# PIC32MZ_BOARD.net
KiCad netlist of a schematic drawn in Altium Designer
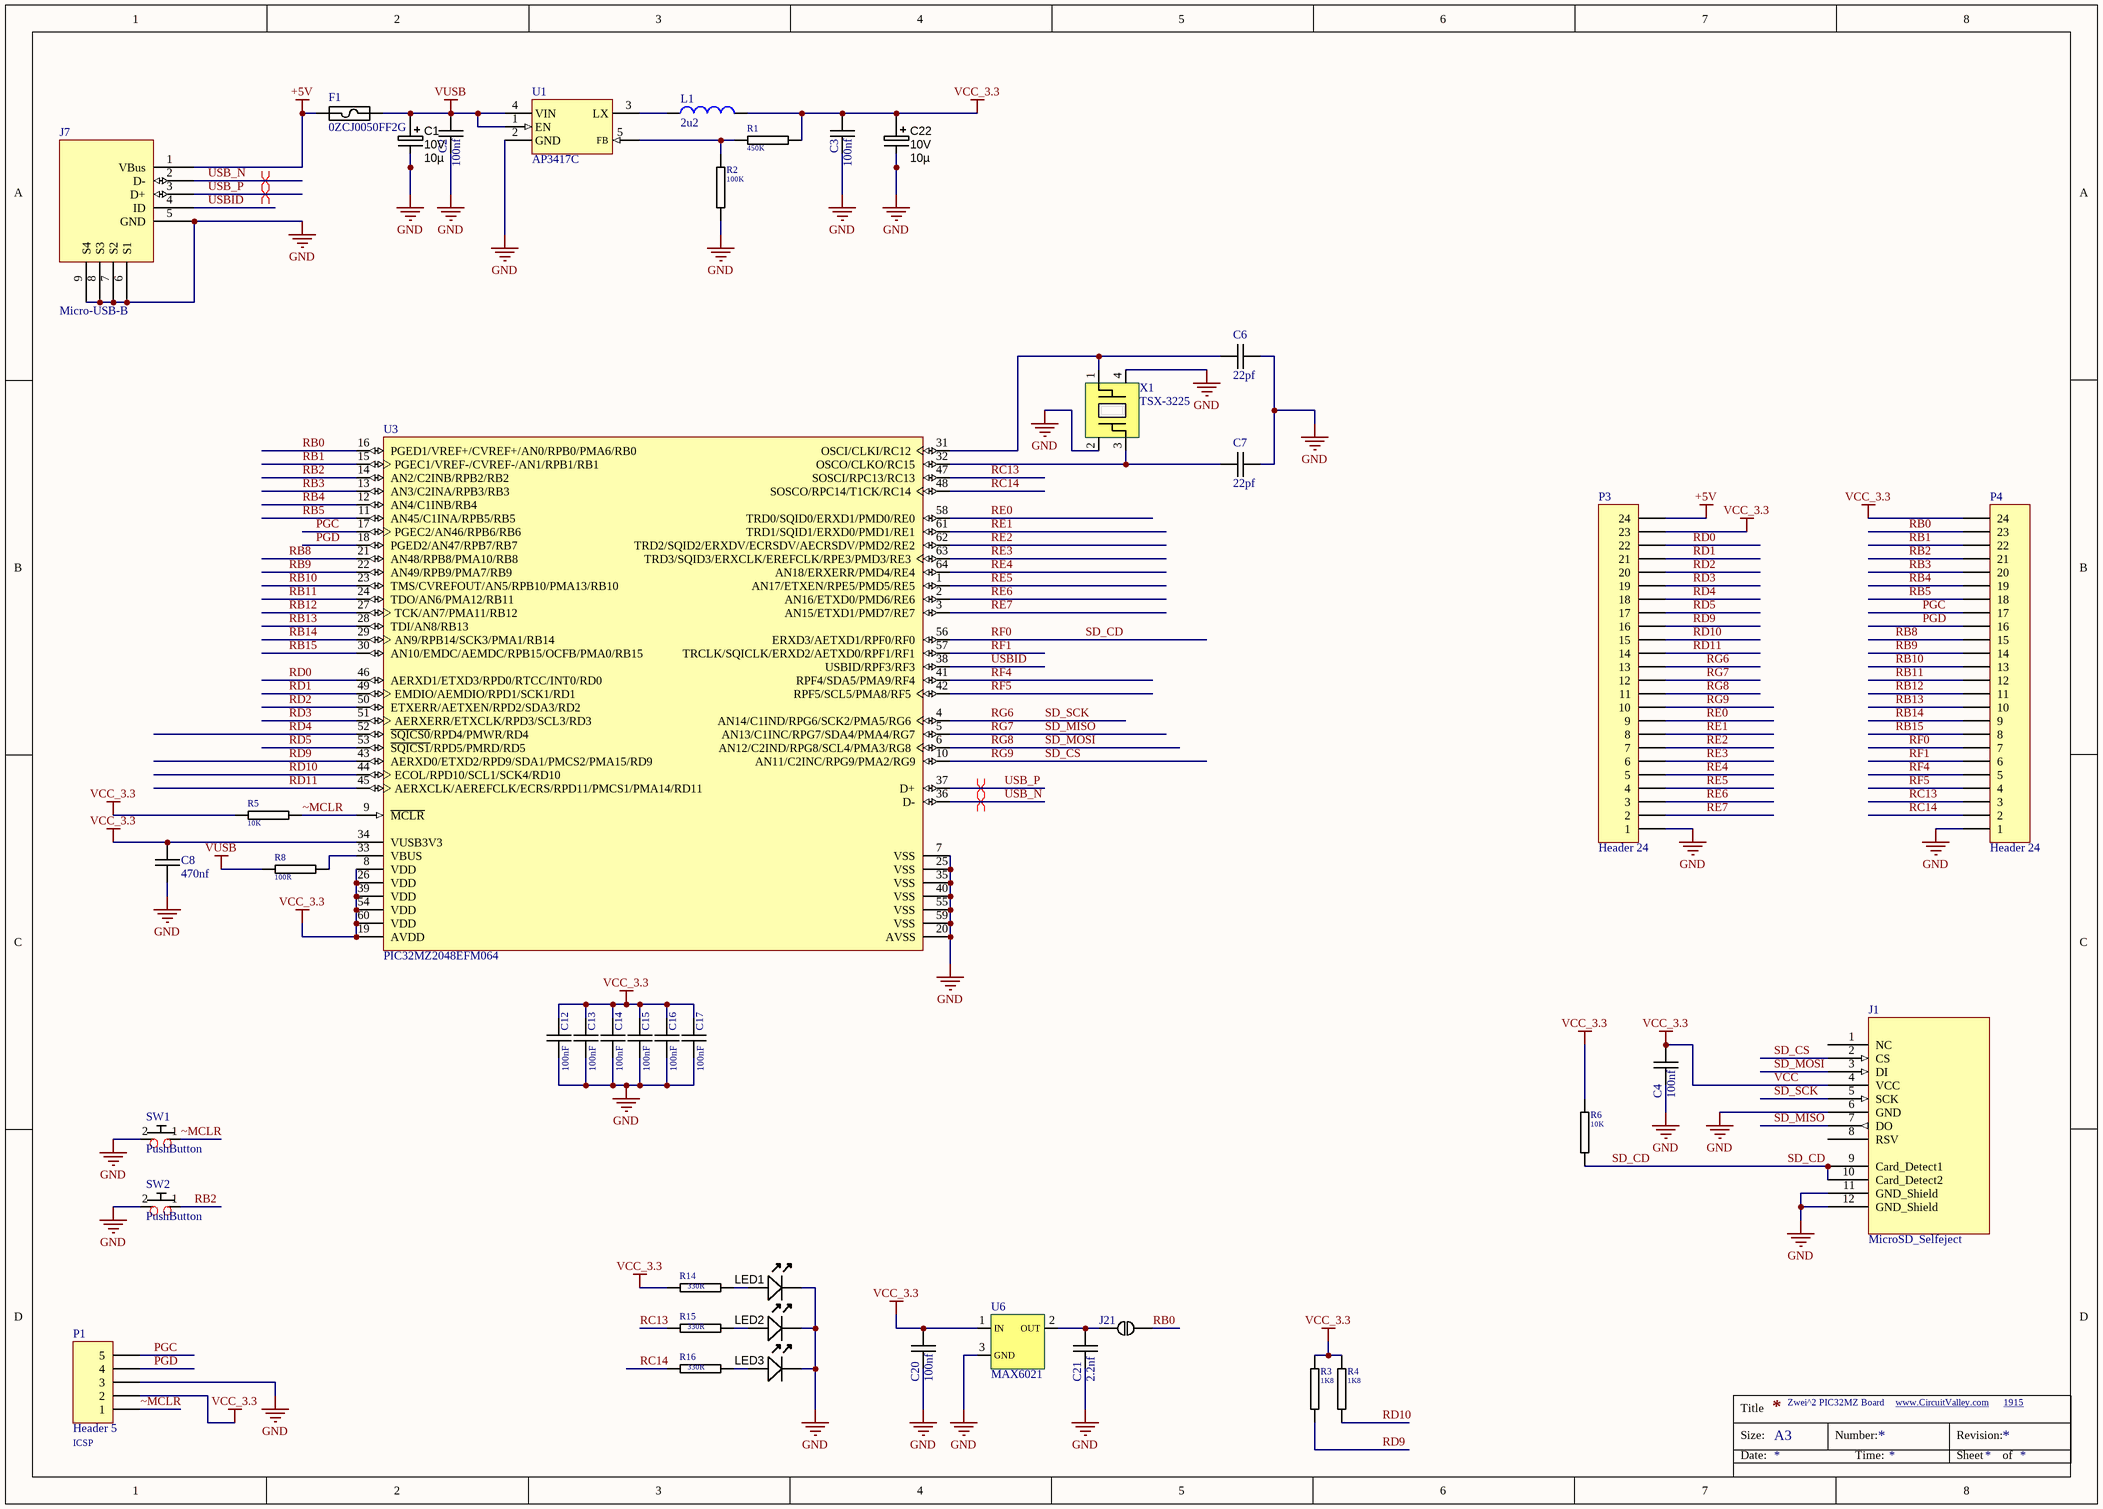
[diagram p0: PIC32MZ_BOARD.SchDoc]

(export (version "E")
  (design (tool "Eeschema 10.0.6"))
  (components
    (comp (ref "C1")
      (value "10µ")
      (footprint "CAPMP3528X210N")
      (description "Capacitor SMD Tantalum 47uF 20% 6.3V 1210")
      (fields (field (name "TOLERANCE") "±20%") (field (name "RATINGS") "10V"))
      (libsource (lib "PBL - Capacitors") (part "CAPT_47u_1210_6V3"))
    )
    (comp (ref "C2")
      (value "100nf")
      (footprint "0603C-GENERIC")
      (description "CAPACITOR 0603 CERAMIC")
      (fields
        (field (name "MANUFACTURER") "Murata Electronics North America")
        (field (name "MANUFACTURER PART NUMBER") "GRM188R60J106ME47D")
      )
      (libsource (lib "Generic") (part "0603C-10UF-6V3-X5R-MUR"))
    )
    (comp (ref "C3")
      (value "100nf")
      (footprint "0603C-GENERIC")
      (description "CAPACITOR 0603 CERAMIC")
      (fields
        (field (name "MANUFACTURER") "Murata Electronics North America")
        (field (name "MANUFACTURER PART NUMBER") "GRM188R60J106ME47D")
      )
      (libsource (lib "Generic") (part "0603C-10UF-6V3-X5R-MUR"))
    )
    (comp (ref "C4")
      (value "100nf")
      (footprint "0603C-GENERIC")
      (description "CAPACITOR 0603 CERAMIC")
      (fields
        (field (name "MANUFACTURER") "Murata Electronics North America")
        (field (name "MANUFACTURER PART NUMBER") "GRM188R60J106ME47D")
      )
      (libsource (lib "Generic") (part "0603C-10UF-6V3-X5R-MUR"))
    )
    (comp (ref "C6")
      (value "22pf")
      (footprint "0603C-GENERIC")
      (description "CAPACITOR 0603 CERAMIC")
      (fields
        (field (name "MANUFACTURER") "Murata Electronics North America")
        (field (name "MANUFACTURER PART NUMBER") "GRM188R60J106ME47D")
      )
      (libsource (lib "Generic") (part "0603C-10UF-6V3-X5R-MUR"))
    )
    (comp (ref "C7")
      (value "22pf")
      (footprint "0603C-GENERIC")
      (description "CAPACITOR 0603 CERAMIC")
      (fields
        (field (name "MANUFACTURER") "Murata Electronics North America")
        (field (name "MANUFACTURER PART NUMBER") "GRM188R60J106ME47D")
      )
      (libsource (lib "Generic") (part "0603C-10UF-6V3-X5R-MUR"))
    )
    (comp (ref "C8")
      (value "470nf")
      (footprint "0603C-GENERIC")
      (description "CAPACITOR 0603 CERAMIC")
      (fields
        (field (name "MANUFACTURER") "Murata Electronics North America")
        (field (name "MANUFACTURER PART NUMBER") "GRM188R60J106ME47D")
      )
      (libsource (lib "Generic") (part "0603C-10UF-6V3-X5R-MUR"))
    )
    (comp (ref "C12")
      (value "100nF")
      (footprint "0603C-GENERIC")
      (description "CAPACITOR 0603 CERAMIC")
      (fields
        (field (name "MANUFACTURER PART NUMBER") "C1608X7R1E104K")
        (field (name "MANUFACTURER") "TDK Corporation")
      )
      (libsource (lib "Generic") (part "0603C-100NF-25V-X7R-TDK"))
    )
    (comp (ref "C13")
      (value "100nF")
      (footprint "0603C-GENERIC")
      (description "CAPACITOR 0603 CERAMIC")
      (fields
        (field (name "MANUFACTURER PART NUMBER") "C1608X7R1E104K")
        (field (name "MANUFACTURER") "TDK Corporation")
      )
      (libsource (lib "Generic") (part "0603C-100NF-25V-X7R-TDK"))
    )
    (comp (ref "C14")
      (value "100nF")
      (footprint "0603C-GENERIC")
      (description "CAPACITOR 0603 CERAMIC")
      (fields
        (field (name "MANUFACTURER PART NUMBER") "C1608X7R1E104K")
        (field (name "MANUFACTURER") "TDK Corporation")
      )
      (libsource (lib "Generic") (part "0603C-100NF-25V-X7R-TDK"))
    )
    (comp (ref "C15")
      (value "100nF")
      (footprint "0603C-GENERIC")
      (description "CAPACITOR 0603 CERAMIC")
      (fields
        (field (name "MANUFACTURER PART NUMBER") "C1608X7R1E104K")
        (field (name "MANUFACTURER") "TDK Corporation")
      )
      (libsource (lib "Generic") (part "0603C-100NF-25V-X7R-TDK"))
    )
    (comp (ref "C16")
      (value "100nF")
      (footprint "0603C-GENERIC")
      (description "CAPACITOR 0603 CERAMIC")
      (fields
        (field (name "MANUFACTURER PART NUMBER") "C1608X7R1E104K")
        (field (name "MANUFACTURER") "TDK Corporation")
      )
      (libsource (lib "Generic") (part "0603C-100NF-25V-X7R-TDK"))
    )
    (comp (ref "C17")
      (value "100nF")
      (footprint "0603C-GENERIC")
      (description "CAPACITOR 0603 CERAMIC")
      (fields
        (field (name "MANUFACTURER PART NUMBER") "C1608X7R1E104K")
        (field (name "MANUFACTURER") "TDK Corporation")
      )
      (libsource (lib "Generic") (part "0603C-100NF-25V-X7R-TDK"))
    )
    (comp (ref "C20")
      (value "100nf")
      (footprint "0603C-GENERIC")
      (description "CAPACITOR 0603 CERAMIC")
      (fields
        (field (name "MANUFACTURER") "Murata Electronics North America")
        (field (name "MANUFACTURER PART NUMBER") "GRM188R60J106ME47D")
      )
      (libsource (lib "Generic") (part "0603C-10UF-6V3-X5R-MUR"))
    )
    (comp (ref "C21")
      (value "2.2nf")
      (footprint "0603C-GENERIC")
      (description "CAPACITOR 0603 CERAMIC")
      (fields
        (field (name "MANUFACTURER") "Murata Electronics North America")
        (field (name "MANUFACTURER PART NUMBER") "GRM188R60J106ME47D")
      )
      (libsource (lib "Generic") (part "0603C-10UF-6V3-X5R-MUR"))
    )
    (comp (ref "C22")
      (value "10µ")
      (footprint "CAPMP3528X210N")
      (description "Capacitor SMD Tantalum 47uF 20% 6.3V 1210")
      (fields (field (name "TOLERANCE") "±20%") (field (name "RATINGS") "10V"))
      (libsource (lib "PBL - Capacitors") (part "CAPT_47u_1210_6V3"))
    )
    (comp (ref "F1")
      (value "0ZCJ0050FF2G")
      (footprint "RESC3216N")
      (description "GENERIC FUSE")
      (libsource (lib "Generic") (part "FUSE-GENERIC"))
    )
    (comp (ref "J1")
      (value "MicroSD_Selfeject")
      (footprint "MicroSD_Selfeject")
      (libsource (lib "MicroSDCard") (part "MicroSD_Selfeject"))
    )
    (comp (ref "J7")
      (value "Micro-USB-B")
      (footprint "10118193-0001lfc")
      (fields (field (name "PART") "10118193-0001lfc"))
      (libsource (lib "USB-MICROB-HW-MC-5F") (part "Micro-USB-B"))
    )
    (comp (ref "J21")
      (value "BYPASS-MINI")
      (footprint "BYPASS-MINI")
      (description "SOLDERDOT BYPASS")
      (libsource (lib "Generic") (part "BYPASS-MINI"))
    )
    (comp (ref "L1")
      (value "2u2")
      (footprint "TAIYO_NRS4018T2R2MDGJ")
      (fields (field (name "PARTNUMBER") "NRS4018T2R2MDGJ"))
      (libsource (lib "Inductor") (part "inductor_smd"))
    )
    (comp (ref "LED1")
      (value "Blue")
      (footprint "LED-0805-K")
      (description "LED 0805 SMD Blue 100mcd 470nm")
      (libsource (lib "PBL - Light Sources") (part "LED_SMD_Blue_0805_100mcd"))
    )
    (comp (ref "LED2")
      (value "Blue")
      (footprint "LED-0805-K")
      (description "LED 0805 SMD Blue 100mcd 470nm")
      (libsource (lib "PBL - Light Sources") (part "LED_SMD_Blue_0805_100mcd"))
    )
    (comp (ref "LED3")
      (value "Blue")
      (footprint "LED-0805-K")
      (description "LED 0805 SMD Blue 100mcd 470nm")
      (libsource (lib "PBL - Light Sources") (part "LED_SMD_Blue_0805_100mcd"))
    )
    (comp (ref "P1")
      (value "Header 5")
      (footprint "HDR1X5")
      (description "Header, 5-Pin")
      (fields (field (name "PUBLISHER") "Altium Limited"))
      (libsource (lib "Miscellaneous Connectors") (part "Header 5"))
    )
    (comp (ref "P3")
      (value "Header 24")
      (footprint "HDR1X24")
      (description "Header, 24-Pin")
      (fields (field (name "PUBLISHER") "Altium Limited"))
      (libsource (lib "Miscellaneous Connectors") (part "Header 24"))
    )
    (comp (ref "P4")
      (value "Header 24")
      (footprint "HDR1X24")
      (description "Header, 24-Pin")
      (fields (field (name "PUBLISHER") "Altium Limited"))
      (libsource (lib "") (part "Header 24_1"))
    )
    (comp (ref "R1")
      (value "450K")
      (footprint "0603R-10K")
      (description "GENERIC RESISTOR 0603")
      (fields (field (name "MANUFACTURER") "Stackpole Electronics Inc") (field (name "TOLERANCE") "±1%"))
      (libsource (lib "Generic") (part "0603R-10K"))
    )
    (comp (ref "R2")
      (value "100K")
      (footprint "0603R-10K")
      (description "GENERIC RESISTOR 0603")
      (fields (field (name "MANUFACTURER") "Stackpole Electronics Inc") (field (name "TOLERANCE") "±1%"))
      (libsource (lib "Generic") (part "0603R-10K"))
    )
    (comp (ref "R3")
      (value "1K8")
      (footprint "0603R-10K")
      (description "GENERIC RESISTOR 0603")
      (fields (field (name "MANUFACTURER") "Stackpole Electronics Inc") (field (name "TOLERANCE") "±1%"))
      (libsource (lib "Generic") (part "0603R-10K"))
    )
    (comp (ref "R4")
      (value "1K8")
      (footprint "0603R-10K")
      (description "GENERIC RESISTOR 0603")
      (fields (field (name "MANUFACTURER") "Stackpole Electronics Inc") (field (name "TOLERANCE") "±1%"))
      (libsource (lib "Generic") (part "0603R-10K"))
    )
    (comp (ref "R5")
      (value "10K")
      (footprint "0603R-10K")
      (description "GENERIC RESISTOR 0603")
      (fields (field (name "MANUFACTURER") "Stackpole Electronics Inc") (field (name "TOLERANCE") "±1%"))
      (libsource (lib "Generic") (part "0603R-10K"))
    )
    (comp (ref "R6")
      (value "10K")
      (footprint "0603R-10K")
      (description "GENERIC RESISTOR 0603")
      (fields (field (name "MANUFACTURER") "Stackpole Electronics Inc") (field (name "TOLERANCE") "±1%"))
      (libsource (lib "Generic") (part "0603R-10K"))
    )
    (comp (ref "R8")
      (value "100R")
      (footprint "0603R-10K")
      (description "GENERIC RESISTOR 0603")
      (fields (field (name "MANUFACTURER") "Stackpole Electronics Inc") (field (name "TOLERANCE") "±1%"))
      (libsource (lib "Generic") (part "0603R-10K"))
    )
    (comp (ref "R14")
      (value "330R")
      (footprint "0603R-10K")
      (description "GENERIC RESISTOR 0603")
      (fields (field (name "MANUFACTURER") "Stackpole Electronics Inc") (field (name "TOLERANCE") "±1%"))
      (libsource (lib "Generic") (part "0603R-10K"))
    )
    (comp (ref "R15")
      (value "330R")
      (footprint "0603R-10K")
      (description "GENERIC RESISTOR 0603")
      (fields (field (name "MANUFACTURER") "Stackpole Electronics Inc") (field (name "TOLERANCE") "±1%"))
      (libsource (lib "Generic") (part "0603R-10K"))
    )
    (comp (ref "R16")
      (value "330R")
      (footprint "0603R-10K")
      (description "GENERIC RESISTOR 0603")
      (fields (field (name "MANUFACTURER") "Stackpole Electronics Inc") (field (name "TOLERANCE") "±1%"))
      (libsource (lib "Generic") (part "0603R-10K"))
    )
    (comp (ref "SW1")
      (value "PushButton")
      (footprint "PushButtonGrid5.08x3.81")
      (libsource (lib "PushSwitchSmall") (part "PushButton"))
    )
    (comp (ref "SW2")
      (value "PushButton")
      (footprint "PushButtonGrid5.08x3.81")
      (libsource (lib "PushSwitchSmall") (part "PushButton"))
    )
    (comp (ref "U1") (value "AP3417C") (footprint "SOT23-5") (libsource (lib "cvlib") (part "AP3417C")))
    (comp (ref "U3")
      (value "PIC32MZ2048EFM064")
      (footprint "MCHP-QFP-PT64_V")
      (libsource (lib "microchip_my") (part "PIC32MZ2048EFM064"))
    )
    (comp (ref "U6") (value "MAX6021") (footprint "SOT23-3") (libsource (lib "cvlib") (part "MAX6021_Ref")))
    (comp (ref "X1")
      (value "TSX-3225")
      (footprint "Active Oscillator 2520")
      (libsource (lib "Crystal_and_oscillator") (part "Crstal_passive_2520"))
    )
  )
  (nets
    (net (code "1") (name "+5V") (class "Default")
      (node (ref "F1") (pin "1") (pintype "passive"))
      (node (ref "J7") (pin "1") (pinfunction "VBus_1") (pintype "power_in"))
      (node (ref "P3") (pin "24") (pinfunction "24_24") (pintype "passive"))
    )
    (net (code "2") (name "/PGC") (class "Default")
      (node (ref "P1") (pin "5") (pinfunction "5_5") (pintype "passive"))
      (node (ref "P4") (pin "17") (pinfunction "17_17") (pintype "passive"))
      (node (ref "U3") (pin "17") (pinfunction "PGEC2/AN46/RPB6/RB6_17") (pintype "bidirectional"))
    )
    (net (code "3") (name "/PGD") (class "Default")
      (node (ref "P1") (pin "4") (pinfunction "4_4") (pintype "passive"))
      (node (ref "P4") (pin "16") (pinfunction "16_16") (pintype "passive"))
      (node (ref "U3") (pin "18") (pinfunction "PGED2/AN47/RPB7/RB7_18") (pintype "bidirectional"))
    )
    (net (code "4") (name "/RB0") (class "Default")
      (node (ref "J21") (pin "1") (pinfunction "1_1") (pintype "passive"))
      (node (ref "P4") (pin "23") (pinfunction "23_23") (pintype "passive"))
      (node (ref "U3") (pin "16") (pinfunction "PGED1/VREF+/CVREF+/AN0/RPB0/PMA6/RB0_16") (pintype "bidirectional"))
    )
    (net (code "5") (name "/RB1") (class "Default")
      (node (ref "P4") (pin "22") (pinfunction "22_22") (pintype "passive"))
      (node (ref "U3") (pin "15") (pinfunction "PGEC1/VREF-/CVREF-/AN1/RPB1/RB1_15") (pintype "bidirectional"))
    )
    (net (code "6") (name "/RB2") (class "Default")
      (node (ref "P4") (pin "21") (pinfunction "21_21") (pintype "passive"))
      (node (ref "SW2") (pin "1") (pinfunction "P1_1") (pintype "passive"))
      (node (ref "U3") (pin "14") (pinfunction "AN2/C2INB/RPB2/RB2_14") (pintype "bidirectional"))
    )
    (net (code "7") (name "/RB3") (class "Default")
      (node (ref "P4") (pin "20") (pinfunction "20_20") (pintype "passive"))
      (node (ref "U3") (pin "13") (pinfunction "AN3/C2INA/RPB3/RB3_13") (pintype "bidirectional"))
    )
    (net (code "8") (name "/RB4") (class "Default")
      (node (ref "P4") (pin "19") (pinfunction "19_19") (pintype "passive"))
      (node (ref "U3") (pin "12") (pinfunction "AN4/C1INB/RB4_12") (pintype "bidirectional"))
    )
    (net (code "9") (name "/RB5") (class "Default")
      (node (ref "P4") (pin "18") (pinfunction "18_18") (pintype "passive"))
      (node (ref "U3") (pin "11") (pinfunction "AN45/C1INA/RPB5/RB5_11") (pintype "bidirectional"))
    )
    (net (code "10") (name "/RB8") (class "Default")
      (node (ref "P4") (pin "15") (pinfunction "15_15") (pintype "passive"))
      (node (ref "U3") (pin "21") (pinfunction "AN48/RPB8/PMA10/RB8_21") (pintype "bidirectional"))
    )
    (net (code "11") (name "/RB9") (class "Default")
      (node (ref "P4") (pin "14") (pinfunction "14_14") (pintype "passive"))
      (node (ref "U3") (pin "22") (pinfunction "AN49/RPB9/PMA7/RB9_22") (pintype "bidirectional"))
    )
    (net (code "12") (name "/RB10") (class "Default")
      (node (ref "P4") (pin "13") (pinfunction "13_13") (pintype "passive"))
      (node (ref "U3") (pin "23") (pinfunction "TMS/CVREFOUT/AN5/RPB10/PMA13/RB10_23") (pintype "bidirectional"))
    )
    (net (code "13") (name "/RB11") (class "Default")
      (node (ref "P4") (pin "12") (pinfunction "12_12") (pintype "passive"))
      (node (ref "U3") (pin "24") (pinfunction "TDO/AN6/PMA12/RB11_24") (pintype "bidirectional"))
    )
    (net (code "14") (name "/RB12") (class "Default")
      (node (ref "P4") (pin "11") (pinfunction "11_11") (pintype "passive"))
      (node (ref "U3") (pin "27") (pinfunction "TCK/AN7/PMA11/RB12_27") (pintype "bidirectional"))
    )
    (net (code "15") (name "/RB13") (class "Default")
      (node (ref "P4") (pin "10") (pinfunction "10_10") (pintype "passive"))
      (node (ref "U3") (pin "28") (pinfunction "TDI/AN8/RB13_28") (pintype "bidirectional"))
    )
    (net (code "16") (name "/RB14") (class "Default")
      (node (ref "P4") (pin "9") (pinfunction "9_9") (pintype "passive"))
      (node (ref "U3") (pin "29") (pinfunction "AN9/RPB14/SCK3/PMA1/RB14_29") (pintype "bidirectional"))
    )
    (net (code "17") (name "/RB15") (class "Default")
      (node (ref "P4") (pin "8") (pinfunction "8_8") (pintype "passive"))
      (node (ref "U3") (pin "30") (pinfunction "AN10/EMDC/AEMDC/RPB15/OCFB/PMA0/RB15_30") (pintype "bidirectional"))
    )
    (net (code "18") (name "/RC13") (class "Default")
      (node (ref "P4") (pin "3") (pinfunction "3_3") (pintype "passive"))
      (node (ref "R15") (pin "1") (pintype "passive"))
      (node (ref "U3") (pin "47") (pinfunction "SOSCI/RPC13/RC13_47") (pintype "bidirectional"))
    )
    (net (code "19") (name "/RC14") (class "Default")
      (node (ref "P4") (pin "2") (pinfunction "2_2") (pintype "passive"))
      (node (ref "R16") (pin "1") (pintype "passive"))
      (node (ref "U3") (pin "48") (pinfunction "SOSCO/RPC14/T1CK/RC14_48") (pintype "bidirectional"))
    )
    (net (code "20") (name "/RD0") (class "Default")
      (node (ref "P3") (pin "22") (pinfunction "22_22") (pintype "passive"))
      (node (ref "U3") (pin "46") (pinfunction "AERXD1/ETXD3/RPD0/RTCC/INT0/RD0_46") (pintype "bidirectional"))
    )
    (net (code "21") (name "/RD1") (class "Default")
      (node (ref "P3") (pin "21") (pinfunction "21_21") (pintype "passive"))
      (node (ref "U3") (pin "49") (pinfunction "EMDIO/AEMDIO/RPD1/SCK1/RD1_49") (pintype "bidirectional"))
    )
    (net (code "22") (name "/RD2") (class "Default")
      (node (ref "P3") (pin "20") (pinfunction "20_20") (pintype "passive"))
      (node (ref "U3") (pin "50") (pinfunction "ETXERR/AETXEN/RPD2/SDA3/RD2_50") (pintype "bidirectional"))
    )
    (net (code "23") (name "/RD3") (class "Default")
      (node (ref "P3") (pin "19") (pinfunction "19_19") (pintype "passive"))
      (node (ref "U3") (pin "51") (pinfunction "AERXERR/ETXCLK/RPD3/SCL3/RD3_51") (pintype "bidirectional"))
    )
    (net (code "24") (name "/RD4") (class "Default")
      (node (ref "P3") (pin "18") (pinfunction "18_18") (pintype "passive"))
      (node (ref "U3") (pin "52") (pinfunction "~{SQICS0}/RPD4/PMWR/RD4_52") (pintype "bidirectional"))
    )
    (net (code "25") (name "/RD5") (class "Default")
      (node (ref "P3") (pin "17") (pinfunction "17_17") (pintype "passive"))
      (node (ref "U3") (pin "53") (pinfunction "~{SQICS1}/RPD5/PMRD/RD5_53") (pintype "bidirectional"))
    )
    (net (code "26") (name "/RD9") (class "Default")
      (node (ref "P3") (pin "16") (pinfunction "16_16") (pintype "passive"))
      (node (ref "R3") (pin "1") (pintype "passive"))
      (node (ref "U3") (pin "43") (pinfunction "AERXD0/ETXD2/RPD9/SDA1/PMCS2/PMA15/RD9_43") (pintype "bidirectional"))
    )
    (net (code "27") (name "/RD10") (class "Default")
      (node (ref "P3") (pin "15") (pinfunction "15_15") (pintype "passive"))
      (node (ref "R4") (pin "1") (pintype "passive"))
      (node (ref "U3") (pin "44") (pinfunction "ECOL/RPD10/SCL1/SCK4/RD10_44") (pintype "bidirectional"))
    )
    (net (code "28") (name "/RD11") (class "Default")
      (node (ref "P3") (pin "14") (pinfunction "14_14") (pintype "passive"))
      (node (ref "U3") (pin "45") (pinfunction "AERXCLK/AEREFCLK/ECRS/RPD11/PMCS1/PMA14/RD11_45") (pintype "bidirectional"))
    )
    (net (code "29") (name "/RE0") (class "Default")
      (node (ref "P3") (pin "9") (pinfunction "9_9") (pintype "passive"))
      (node (ref "U3") (pin "58") (pinfunction "TRD0/SQID0/ERXD1/PMD0/RE0_58") (pintype "bidirectional"))
    )
    (net (code "30") (name "/RE1") (class "Default")
      (node (ref "P3") (pin "8") (pinfunction "8_8") (pintype "passive"))
      (node (ref "U3") (pin "61") (pinfunction "TRD1/SQID1/ERXD0/PMD1/RE1_61") (pintype "bidirectional"))
    )
    (net (code "31") (name "/RE2") (class "Default")
      (node (ref "P3") (pin "7") (pinfunction "7_7") (pintype "passive"))
      (node (ref "U3") (pin "62") (pinfunction "TRD2/SQID2/ERXDV/ECRSDV/AECRSDV/PMD2/RE2_62") (pintype "bidirectional"))
    )
    (net (code "32") (name "/RE3") (class "Default")
      (node (ref "P3") (pin "6") (pinfunction "6_6") (pintype "passive"))
      (node (ref "U3") (pin "63") (pinfunction "TRD3/SQID3/ERXCLK/EREFCLK/RPE3/PMD3/RE3_63") (pintype "bidirectional"))
    )
    (net (code "33") (name "/RE4") (class "Default")
      (node (ref "P3") (pin "5") (pinfunction "5_5") (pintype "passive"))
      (node (ref "U3") (pin "64") (pinfunction "AN18/ERXERR/PMD4/RE4_64") (pintype "bidirectional"))
    )
    (net (code "34") (name "/RE5") (class "Default")
      (node (ref "P3") (pin "4") (pinfunction "4_4") (pintype "passive"))
      (node (ref "U3") (pin "1") (pinfunction "AN17/ETXEN/RPE5/PMD5/RE5_1") (pintype "bidirectional"))
    )
    (net (code "35") (name "/RE6") (class "Default")
      (node (ref "P3") (pin "3") (pinfunction "3_3") (pintype "passive"))
      (node (ref "U3") (pin "2") (pinfunction "AN16/ETXD0/PMD6/RE6_2") (pintype "bidirectional"))
    )
    (net (code "36") (name "/RE7") (class "Default")
      (node (ref "P3") (pin "2") (pinfunction "2_2") (pintype "passive"))
      (node (ref "U3") (pin "3") (pinfunction "AN15/ETXD1/PMD7/RE7_3") (pintype "bidirectional"))
    )
    (net (code "37") (name "/RF0") (class "Default")
      (node (ref "J1") (pin "10") (pinfunction "Card_Detect2_10") (pintype "passive"))
      (node (ref "J1") (pin "9") (pinfunction "Card_Detect1_9") (pintype "passive"))
      (node (ref "P4") (pin "7") (pinfunction "7_7") (pintype "passive"))
      (node (ref "R6") (pin "1") (pintype "passive"))
      (node (ref "U3") (pin "56") (pinfunction "ERXD3/AETXD1/RPF0/RF0_56") (pintype "bidirectional"))
    )
    (net (code "38") (name "/RF1") (class "Default")
      (node (ref "P4") (pin "6") (pinfunction "6_6") (pintype "passive"))
      (node (ref "U3") (pin "57") (pinfunction "TRCLK/SQICLK/ERXD2/AETXD0/RPF1/RF1_57") (pintype "bidirectional"))
    )
    (net (code "39") (name "/RF4") (class "Default")
      (node (ref "P4") (pin "5") (pinfunction "5_5") (pintype "passive"))
      (node (ref "U3") (pin "41") (pinfunction "RPF4/SDA5/PMA9/RF4_41") (pintype "bidirectional"))
    )
    (net (code "40") (name "/RF5") (class "Default")
      (node (ref "P4") (pin "4") (pinfunction "4_4") (pintype "passive"))
      (node (ref "U3") (pin "42") (pinfunction "RPF5/SCL5/PMA8/RF5_42") (pintype "bidirectional"))
    )
    (net (code "41") (name "/RG6") (class "Default")
      (node (ref "J1") (pin "5") (pinfunction "SCK_5") (pintype "input"))
      (node (ref "P3") (pin "13") (pinfunction "13_13") (pintype "passive"))
      (node (ref "U3") (pin "4") (pinfunction "AN14/C1IND/RPG6/SCK2/PMA5/RG6_4") (pintype "bidirectional"))
    )
    (net (code "42") (name "/RG7") (class "Default")
      (node (ref "J1") (pin "7") (pinfunction "DO_7") (pintype "output"))
      (node (ref "P3") (pin "12") (pinfunction "12_12") (pintype "passive"))
      (node (ref "U3") (pin "5") (pinfunction "AN13/C1INC/RPG7/SDA4/PMA4/RG7_5") (pintype "bidirectional"))
    )
    (net (code "43") (name "/RG8") (class "Default")
      (node (ref "J1") (pin "3") (pinfunction "DI_3") (pintype "input"))
      (node (ref "P3") (pin "11") (pinfunction "11_11") (pintype "passive"))
      (node (ref "U3") (pin "6") (pinfunction "AN12/C2IND/RPG8/SCL4/PMA3/RG8_6") (pintype "bidirectional"))
    )
    (net (code "44") (name "/RG9") (class "Default")
      (node (ref "J1") (pin "2") (pinfunction "CS_2") (pintype "input"))
      (node (ref "P3") (pin "10") (pinfunction "10_10") (pintype "passive"))
      (node (ref "U3") (pin "10") (pinfunction "AN11/C2INC/RPG9/PMA2/RG9_10") (pintype "bidirectional"))
    )
    (net (code "45") (name "/USBID") (class "Default")
      (node (ref "J7") (pin "4") (pinfunction "ID_4") (pintype "passive"))
      (node (ref "U3") (pin "38") (pinfunction "USBID/RPF3/RF3_38") (pintype "bidirectional"))
    )
    (net (code "46") (name "/USB_N") (class "Default")
      (node (ref "J7") (pin "2") (pinfunction "D-_2") (pintype "bidirectional"))
      (node (ref "U3") (pin "36") (pinfunction "D-_36") (pintype "bidirectional"))
    )
    (net (code "47") (name "/USB_P") (class "Default")
      (node (ref "J7") (pin "3") (pinfunction "D+_3") (pintype "bidirectional"))
      (node (ref "U3") (pin "37") (pinfunction "D+_37") (pintype "bidirectional"))
    )
    (net (code "48") (name "/~MCLR") (class "Default")
      (node (ref "P1") (pin "1") (pinfunction "1_1") (pintype "passive"))
      (node (ref "R5") (pin "2") (pintype "passive"))
      (node (ref "SW1") (pin "1") (pinfunction "P1_1") (pintype "passive"))
      (node (ref "U3") (pin "9") (pinfunction "~{MCLR}_9") (pintype "input"))
    )
    (net (code "49") (name "GND") (class "Default")
      (node (ref "C1") (pin "2") (pintype "passive"))
      (node (ref "C12") (pin "1") (pintype "passive"))
      (node (ref "C13") (pin "1") (pintype "passive"))
      (node (ref "C14") (pin "1") (pintype "passive"))
      (node (ref "C15") (pin "1") (pintype "passive"))
      (node (ref "C16") (pin "1") (pintype "passive"))
      (node (ref "C17") (pin "1") (pintype "passive"))
      (node (ref "C2") (pin "1") (pintype "passive"))
      (node (ref "C20") (pin "1") (pintype "passive"))
      (node (ref "C21") (pin "1") (pintype "passive"))
      (node (ref "C22") (pin "2") (pintype "passive"))
      (node (ref "C3") (pin "1") (pintype "passive"))
      (node (ref "C4") (pin "1") (pintype "passive"))
      (node (ref "C6") (pin "1") (pintype "passive"))
      (node (ref "C7") (pin "1") (pintype "passive"))
      (node (ref "C8") (pin "2") (pintype "passive"))
      (node (ref "J1") (pin "11") (pinfunction "GND_Shield_11") (pintype "passive"))
      (node (ref "J1") (pin "12") (pinfunction "GND_Shield_12") (pintype "passive"))
      (node (ref "J1") (pin "6") (pinfunction "GND_6") (pintype "power_in"))
      (node (ref "J7") (pin "5") (pinfunction "GND_5") (pintype "power_in"))
      (node (ref "J7") (pin "6") (pinfunction "S1_6") (pintype "passive"))
      (node (ref "J7") (pin "7") (pinfunction "S2_7") (pintype "power_in"))
      (node (ref "J7") (pin "8") (pinfunction "S3_8") (pintype "power_in"))
      (node (ref "J7") (pin "9") (pinfunction "S4_9") (pintype "power_in"))
      (node (ref "LED1") (pin "K") (pinfunction "K_K") (pintype "passive"))
      (node (ref "LED2") (pin "K") (pinfunction "K_K") (pintype "passive"))
      (node (ref "LED3") (pin "K") (pinfunction "K_K") (pintype "passive"))
      (node (ref "P1") (pin "3") (pinfunction "3_3") (pintype "passive"))
      (node (ref "P3") (pin "1") (pinfunction "1_1") (pintype "passive"))
      (node (ref "P4") (pin "1") (pinfunction "1_1") (pintype "passive"))
      (node (ref "R2") (pin "1") (pintype "passive"))
      (node (ref "SW1") (pin "2") (pinfunction "P2_2") (pintype "passive"))
      (node (ref "SW2") (pin "2") (pinfunction "P2_2") (pintype "passive"))
      (node (ref "U1") (pin "2") (pinfunction "GND_2") (pintype "power_in"))
      (node (ref "U3") (pin "20") (pinfunction "AVSS_20") (pintype "power_in"))
      (node (ref "U3") (pin "25") (pinfunction "VSS_25") (pintype "power_in"))
      (node (ref "U3") (pin "35") (pinfunction "VSS_35") (pintype "power_in"))
      (node (ref "U3") (pin "40") (pinfunction "VSS_40") (pintype "power_in"))
      (node (ref "U3") (pin "55") (pinfunction "VSS_55") (pintype "power_in"))
      (node (ref "U3") (pin "59") (pinfunction "VSS_59") (pintype "power_in"))
      (node (ref "U3") (pin "7") (pinfunction "VSS_7") (pintype "power_in"))
      (node (ref "U6") (pin "3") (pinfunction "GND_3") (pintype "power_in"))
      (node (ref "X1") (pin "2") (pinfunction "2_2") (pintype "passive"))
      (node (ref "X1") (pin "4") (pinfunction "4_4") (pintype "passive"))
    )
    (net (code "50") (name "Net-(LED1-PadA)") (class "Default")
      (node (ref "LED1") (pin "A") (pinfunction "A_A") (pintype "passive"))
      (node (ref "R14") (pin "2") (pintype "passive"))
    )
    (net (code "51") (name "Net-(LED2-PadA)") (class "Default")
      (node (ref "LED2") (pin "A") (pinfunction "A_A") (pintype "passive"))
      (node (ref "R15") (pin "2") (pintype "passive"))
    )
    (net (code "52") (name "Net-(LED3-PadA)") (class "Default")
      (node (ref "LED3") (pin "A") (pinfunction "A_A") (pintype "passive"))
      (node (ref "R16") (pin "2") (pintype "passive"))
    )
    (net (code "53") (name "Net-(U1-FB)") (class "Default")
      (node (ref "R1") (pin "1") (pintype "passive"))
      (node (ref "R2") (pin "2") (pintype "passive"))
      (node (ref "U1") (pin "5") (pinfunction "FB_5") (pintype "input"))
    )
    (net (code "54") (name "Net-(U1-LX)") (class "Default")
      (node (ref "L1") (pin "1") (pinfunction "1_1") (pintype "passive"))
      (node (ref "U1") (pin "3") (pinfunction "LX_3") (pintype "passive"))
    )
    (net (code "55") (name "Net-(U3-OSCI{slash}CLKI{slash}RC12)") (class "Default")
      (node (ref "C6") (pin "2") (pintype "passive"))
      (node (ref "U3") (pin "31") (pinfunction "OSCI/CLKI/RC12_31") (pintype "bidirectional"))
      (node (ref "X1") (pin "1") (pinfunction "1_1") (pintype "passive"))
    )
    (net (code "56") (name "Net-(U3-OSCO{slash}CLKO{slash}RC15)") (class "Default")
      (node (ref "C7") (pin "2") (pintype "passive"))
      (node (ref "U3") (pin "32") (pinfunction "OSCO/CLKO/RC15_32") (pintype "bidirectional"))
      (node (ref "X1") (pin "3") (pinfunction "3_3") (pintype "passive"))
    )
    (net (code "57") (name "Net-(U3-VBUS)") (class "Default")
      (node (ref "R8") (pin "2") (pintype "passive"))
      (node (ref "U3") (pin "33") (pinfunction "VBUS_33") (pintype "power_in"))
    )
    (net (code "58") (name "Net-(U6-OUT)") (class "Default")
      (node (ref "C21") (pin "2") (pintype "passive"))
      (node (ref "J21") (pin "2") (pinfunction "2_2") (pintype "passive"))
      (node (ref "U6") (pin "2") (pinfunction "OUT_2") (pintype "power_in"))
    )
    (net (code "59") (name "VCC_3.3") (class "Default")
      (node (ref "C12") (pin "2") (pintype "passive"))
      (node (ref "C13") (pin "2") (pintype "passive"))
      (node (ref "C14") (pin "2") (pintype "passive"))
      (node (ref "C15") (pin "2") (pintype "passive"))
      (node (ref "C16") (pin "2") (pintype "passive"))
      (node (ref "C17") (pin "2") (pintype "passive"))
      (node (ref "C20") (pin "2") (pintype "passive"))
      (node (ref "C22") (pin "1") (pintype "passive"))
      (node (ref "C3") (pin "2") (pintype "passive"))
      (node (ref "C4") (pin "2") (pintype "passive"))
      (node (ref "C8") (pin "1") (pintype "passive"))
      (node (ref "J1") (pin "4") (pinfunction "VCC_4") (pintype "power_in"))
      (node (ref "L1") (pin "2") (pinfunction "2_2") (pintype "passive"))
      (node (ref "P1") (pin "2") (pinfunction "2_2") (pintype "passive"))
      (node (ref "P3") (pin "23") (pinfunction "23_23") (pintype "passive"))
      (node (ref "P4") (pin "24") (pinfunction "24_24") (pintype "passive"))
      (node (ref "R1") (pin "2") (pintype "passive"))
      (node (ref "R14") (pin "1") (pintype "passive"))
      (node (ref "R3") (pin "2") (pintype "passive"))
      (node (ref "R4") (pin "2") (pintype "passive"))
      (node (ref "R5") (pin "1") (pintype "passive"))
      (node (ref "R6") (pin "2") (pintype "passive"))
      (node (ref "U3") (pin "19") (pinfunction "AVDD_19") (pintype "power_in"))
      (node (ref "U3") (pin "26") (pinfunction "VDD_26") (pintype "power_in"))
      (node (ref "U3") (pin "34") (pinfunction "VUSB3V3_34") (pintype "power_in"))
      (node (ref "U3") (pin "39") (pinfunction "VDD_39") (pintype "power_in"))
      (node (ref "U3") (pin "54") (pinfunction "VDD_54") (pintype "power_in"))
      (node (ref "U3") (pin "60") (pinfunction "VDD_60") (pintype "power_in"))
      (node (ref "U3") (pin "8") (pinfunction "VDD_8") (pintype "power_in"))
      (node (ref "U6") (pin "1") (pinfunction "IN_1") (pintype "power_in"))
    )
    (net (code "60") (name "VUSB") (class "Default")
      (node (ref "C1") (pin "1") (pintype "passive"))
      (node (ref "C2") (pin "2") (pintype "passive"))
      (node (ref "F1") (pin "2") (pintype "passive"))
      (node (ref "R8") (pin "1") (pintype "passive"))
      (node (ref "U1") (pin "1") (pinfunction "EN_1") (pintype "input"))
      (node (ref "U1") (pin "4") (pinfunction "VIN_4") (pintype "power_in"))
    )
    (net (code "61") (name "unconnected-(J1-NC-Pad1)") (class "Default")
      (node (ref "J1") (pin "1") (pinfunction "NC_1") (pintype "passive"))
    )
    (net (code "62") (name "unconnected-(J1-RSV-Pad8)") (class "Default")
      (node (ref "J1") (pin "8") (pinfunction "RSV_8") (pintype "passive"))
    )
  )
)
